# LM1117_Variable_Regulator_1_25VDC-10VDC.net
KiCad netlist of a schematic drawn in EAGLE
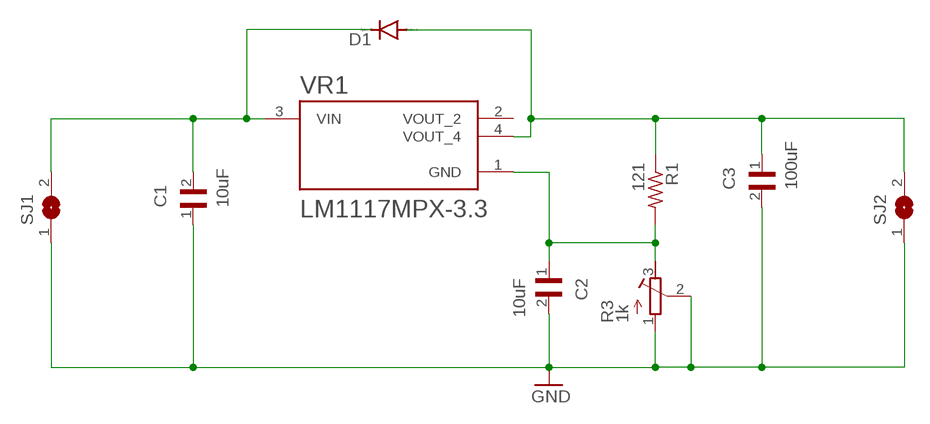
[diagram p0: schematic, sheet 1]

(export (version "E")
  (design (tool "Eeschema 10.0.6"))
  (components
    (comp (ref "C1")
      (value "10uF")
      (footprint "eagle-import:CAPC1608X100N")
      (fields (field (name "MF") "Murata") (field (name "MP") "GRM188C81C106MA73J"))
      (libsource (lib "eagle-import") (part "GRM188C81C106MA73J"))
    )
    (comp (ref "C2")
      (value "10uF")
      (footprint "eagle-import:CAPC1608X100N")
      (fields (field (name "MF") "Murata") (field (name "MP") "GRM188C81C106MA73J"))
      (libsource (lib "eagle-import") (part "GRM188C81C106MA73J"))
    )
    (comp (ref "C3")
      (value "100uF")
      (footprint "eagle-import:CAPPM7343X310N")
      (fields (field (name "MF") "Vishay Sprague") (field (name "MP") "293D107X9016D2TE3"))
      (libsource (lib "eagle-import") (part "293D107X9016D2TE3"))
    )
    (comp (ref "D1")
      (value "DIODE-DO-214AC")
      (footprint "eagle-import:DO-214AC")
      (libsource (lib "eagle-import") (part "DIODE-DO-214AC"))
    )
    (comp (ref "R1")
      (value "121")
      (footprint "eagle-import:R1206")
      (libsource (lib "eagle-import") (part "R-US_R1206"))
    )
    (comp (ref "R3")
      (value "1k")
      (footprint "eagle-import:RTRIM3214W")
      (libsource (lib "eagle-import") (part "R-TRIMM3214W"))
    )
    (comp (ref "SJ1")
      (value "SJW")
      (footprint "eagle-import:SJW")
      (libsource (lib "eagle-import") (part "SJW"))
    )
    (comp (ref "SJ2")
      (value "SJW")
      (footprint "eagle-import:SJW")
      (libsource (lib "eagle-import") (part "SJW"))
    )
    (comp (ref "VR1")
      (value "LM1117MPX-3.3")
      (footprint "eagle-import:VREG_LM1117MPX-3.3")
      (fields (field (name "MF") "Texas Instruments"))
      (libsource (lib "eagle-import") (part "LM1117MPX-3.3"))
    )
  )
  (nets
    (net (code "1") (name "GND") (class "Default")
      (node (ref "C1") (pin "1") (pinfunction "1_1") (pintype "passive"))
      (node (ref "C2") (pin "2") (pinfunction "2_2") (pintype "passive"))
      (node (ref "C3") (pin "2") (pinfunction "2_2") (pintype "passive"))
      (node (ref "R3") (pin "1") (pinfunction "A_1") (pintype "passive"))
      (node (ref "R3") (pin "2") (pinfunction "S_2") (pintype "passive"))
      (node (ref "SJ1") (pin "1") (pinfunction "1_1") (pintype "passive"))
      (node (ref "SJ2") (pin "1") (pinfunction "1_1") (pintype "passive"))
    )
    (net (code "2") (name "Net-(R3-E)") (class "Default")
      (node (ref "C2") (pin "1") (pinfunction "1_1") (pintype "passive"))
      (node (ref "R1") (pin "2") (pinfunction "2_2") (pintype "passive"))
      (node (ref "R3") (pin "3") (pinfunction "E_3") (pintype "passive"))
      (node (ref "VR1") (pin "1") (pinfunction "GND_1") (pintype "power_in"))
    )
    (net (code "3") (name "Net-(VR1-VIN)") (class "Default")
      (node (ref "C1") (pin "2") (pinfunction "2_2") (pintype "passive"))
      (node (ref "D1") (pin "C") (pinfunction "C_C") (pintype "passive"))
      (node (ref "SJ1") (pin "2") (pinfunction "2_2") (pintype "passive"))
      (node (ref "VR1") (pin "3") (pinfunction "VIN_3") (pintype "input"))
    )
    (net (code "4") (name "Net-(VR1-VOUT_4)") (class "Default")
      (node (ref "C3") (pin "1") (pinfunction "1_1") (pintype "passive"))
      (node (ref "D1") (pin "A") (pinfunction "A_A") (pintype "passive"))
      (node (ref "R1") (pin "1") (pinfunction "1_1") (pintype "passive"))
      (node (ref "SJ2") (pin "2") (pinfunction "2_2") (pintype "passive"))
      (node (ref "VR1") (pin "4") (pinfunction "VOUT_4_4") (pintype "output"))
    )
    (net (code "5") (name "unconnected-(VR1-VOUT_2-Pad2)") (class "Default")
      (node (ref "VR1") (pin "2") (pinfunction "VOUT_2_2") (pintype "output"))
    )
  )
)
